# Lights.net
KiCad netlist of a schematic drawn in Altium Designer
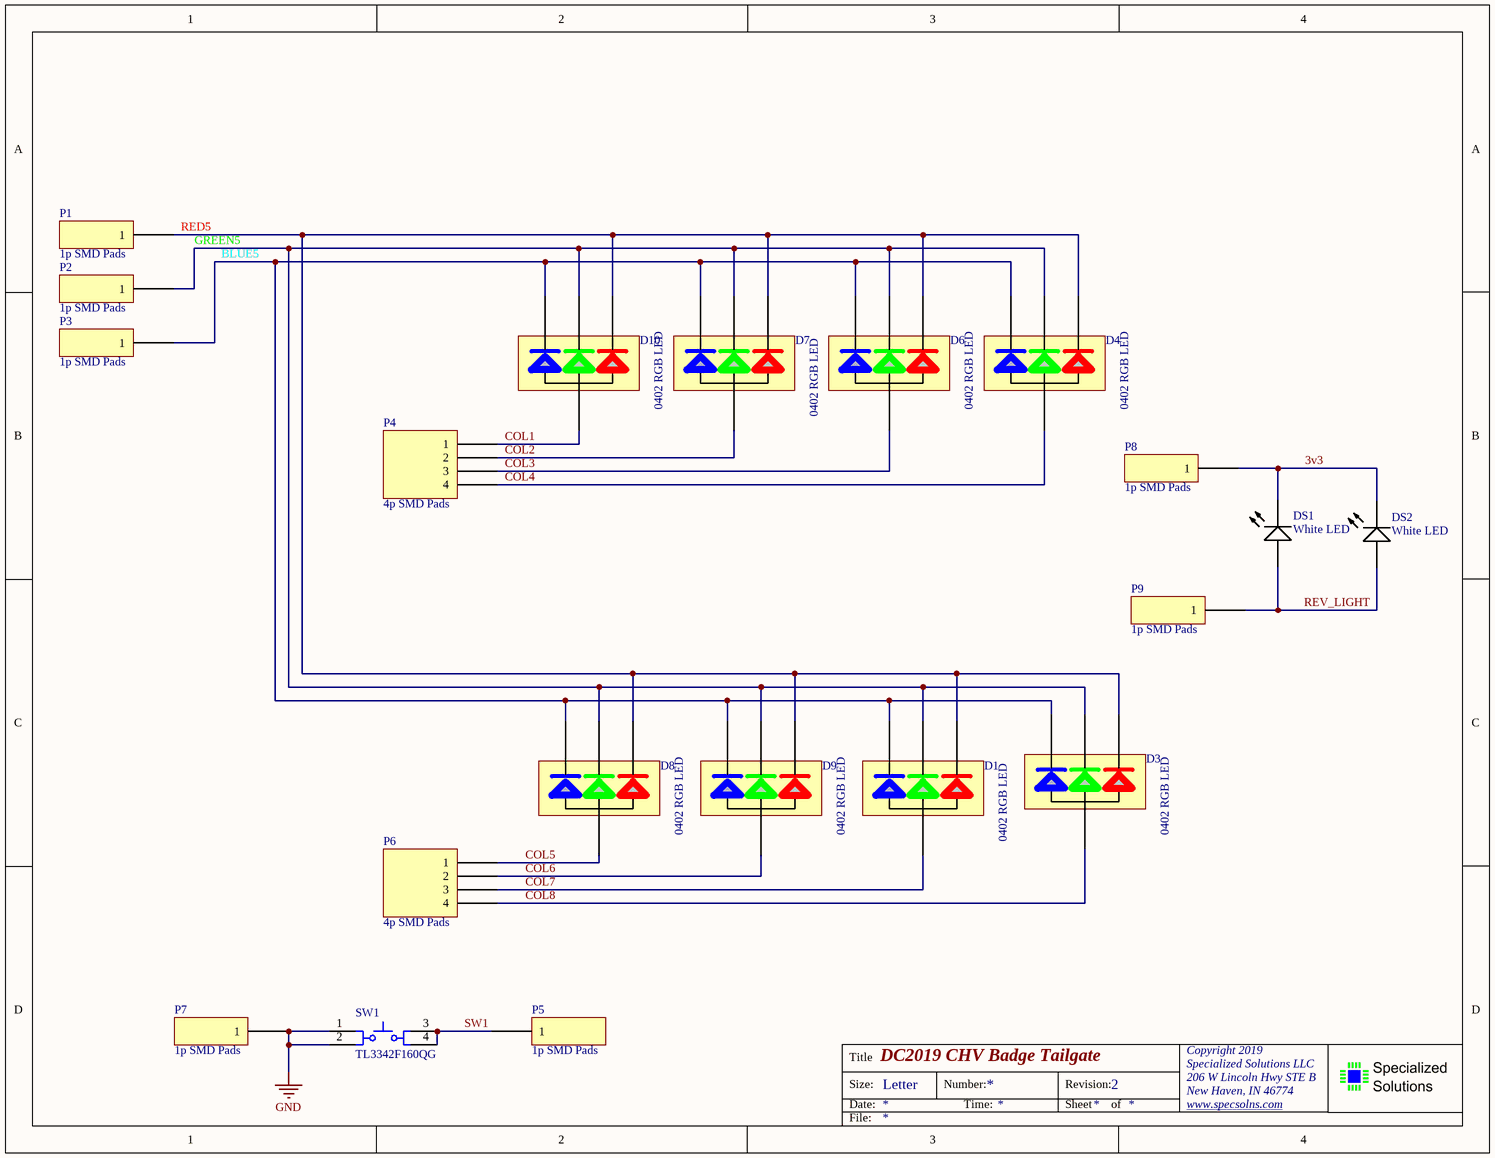
[diagram p0: Lights.SchDoc]

(export (version "E")
  (design (tool "Eeschema 10.0.6"))
  (components
    (comp (ref "D1")
      (value "0402 RGB LED")
      (footprint "0404 RGB LED")
      (libsource (lib "parts (fraker's conflicted copy 2018-10-08)") (part "0402 RGB LED"))
    )
    (comp (ref "D3")
      (value "0402 RGB LED")
      (footprint "0404 RGB LED")
      (libsource (lib "parts (fraker's conflicted copy 2018-10-08)") (part "0402 RGB LED"))
    )
    (comp (ref "D4")
      (value "0402 RGB LED")
      (footprint "0404 RGB LED")
      (libsource (lib "parts (fraker's conflicted copy 2018-10-08)") (part "0402 RGB LED"))
    )
    (comp (ref "D6")
      (value "0402 RGB LED")
      (footprint "0404 RGB LED")
      (libsource (lib "parts (fraker's conflicted copy 2018-10-08)") (part "0402 RGB LED"))
    )
    (comp (ref "D7")
      (value "0402 RGB LED")
      (footprint "0404 RGB LED")
      (libsource (lib "parts (fraker's conflicted copy 2018-10-08)") (part "0402 RGB LED"))
    )
    (comp (ref "D8")
      (value "0402 RGB LED")
      (footprint "0404 RGB LED")
      (libsource (lib "parts (fraker's conflicted copy 2018-10-08)") (part "0402 RGB LED"))
    )
    (comp (ref "D9")
      (value "0402 RGB LED")
      (footprint "0404 RGB LED")
      (libsource (lib "parts (fraker's conflicted copy 2018-10-08)") (part "0402 RGB LED"))
    )
    (comp (ref "D10")
      (value "0402 RGB LED")
      (footprint "0404 RGB LED")
      (libsource (lib "parts (fraker's conflicted copy 2018-10-08)") (part "0402 RGB LED"))
    )
    (comp (ref "DS1")
      (value "White LED")
      (footprint "EVRL-0402-2_V")
      (description "Chip LED, White, 5 V, 10 mA, 30 mW, -40 to 85 degC, 2-Pin SMD (0402), RoHS, Tape and Reel")
      (fields (field (name "MANUFACTURER") "Everlight Electronics"))
      (libsource (lib "Altium Content Vault") (part "LED-WHITE-AK-2"))
    )
    (comp (ref "DS2")
      (value "White LED")
      (footprint "EVRL-0402-2_V")
      (description "Chip LED, White, 5 V, 10 mA, 30 mW, -40 to 85 degC, 2-Pin SMD (0402), RoHS, Tape and Reel")
      (fields (field (name "MANUFACTURER") "Everlight Electronics"))
      (libsource (lib "Altium Content Vault") (part "LED-WHITE-AK-2"))
    )
    (comp (ref "P1") (value "1p SMD Pads") (footprint "1p SMD pad") (libsource (lib "parts") (part "1p SMD")))
    (comp (ref "P2") (value "1p SMD Pads") (footprint "1p SMD pad") (libsource (lib "parts") (part "1p SMD")))
    (comp (ref "P3") (value "1p SMD Pads") (footprint "1p SMD pad") (libsource (lib "parts") (part "1p SMD")))
    (comp (ref "P4") (value "4p SMD Pads") (footprint "4p SMD pad") (libsource (lib "parts") (part "4p SMD")))
    (comp (ref "P5")
      (value "1p SMD Pads")
      (footprint "1p SMD pad")
      (libsource (lib "parts (carol's conflicted copy 2019-04-30)") (part "1p SMD"))
    )
    (comp (ref "P6") (value "4p SMD Pads") (footprint "4p SMD pad") (libsource (lib "parts") (part "4p SMD")))
    (comp (ref "P7") (value "1p SMD Pads") (footprint "1p SMD pad") (libsource (lib "") (part "1p SMD_1")))
    (comp (ref "P8") (value "1p SMD Pads") (footprint "1p SMD pad") (libsource (lib "parts") (part "1p SMD")))
    (comp (ref "P9") (value "1p SMD Pads") (footprint "1p SMD pad") (libsource (lib "parts") (part "1p SMD")))
    (comp (ref "SW1")
      (value "TL3342F160QG")
      (footprint "ESWI-TL3342F160QG_V")
      (description "Switch, Tactile, SPST-NO, 50 mA, 12 V, 4-Pin SMD, RoHS, Tape and Reel")
      (fields (field (name "TOLERANCE") "20%"))
      (libsource (lib "Altium Content Vault") (part "SW-SPST-NO-4"))
    )
  )
  (nets
    (net (code "1") (name "/3v3") (class "Default")
      (node (ref "DS1") (pin "2") (pinfunction "K_2") (pintype "passive"))
      (node (ref "DS2") (pin "2") (pinfunction "K_2") (pintype "passive"))
      (node (ref "P8") (pin "1") (pinfunction "1_1") (pintype "passive"))
    )
    (net (code "2") (name "/BLUE5") (class "Default")
      (node (ref "D1") (pin "4") (pintype "passive"))
      (node (ref "D10") (pin "4") (pintype "passive"))
      (node (ref "D3") (pin "4") (pintype "passive"))
      (node (ref "D4") (pin "4") (pintype "passive"))
      (node (ref "D6") (pin "4") (pintype "passive"))
      (node (ref "D7") (pin "4") (pintype "passive"))
      (node (ref "D8") (pin "4") (pintype "passive"))
      (node (ref "D9") (pin "4") (pintype "passive"))
      (node (ref "P3") (pin "1") (pinfunction "1_1") (pintype "passive"))
    )
    (net (code "3") (name "/COL1") (class "Default")
      (node (ref "D10") (pin "1") (pintype "passive"))
      (node (ref "P4") (pin "1") (pinfunction "1_1") (pintype "passive"))
    )
    (net (code "4") (name "/COL2") (class "Default")
      (node (ref "D7") (pin "1") (pintype "passive"))
      (node (ref "P4") (pin "2") (pinfunction "2_2") (pintype "passive"))
    )
    (net (code "5") (name "/COL3") (class "Default")
      (node (ref "D6") (pin "1") (pintype "passive"))
      (node (ref "P4") (pin "3") (pinfunction "3_3") (pintype "passive"))
    )
    (net (code "6") (name "/COL4") (class "Default")
      (node (ref "D4") (pin "1") (pintype "passive"))
      (node (ref "P4") (pin "4") (pinfunction "4_4") (pintype "passive"))
    )
    (net (code "7") (name "/COL5") (class "Default")
      (node (ref "D8") (pin "1") (pintype "passive"))
      (node (ref "P6") (pin "1") (pinfunction "1_1") (pintype "passive"))
    )
    (net (code "8") (name "/COL6") (class "Default")
      (node (ref "D9") (pin "1") (pintype "passive"))
      (node (ref "P6") (pin "2") (pinfunction "2_2") (pintype "passive"))
    )
    (net (code "9") (name "/COL7") (class "Default")
      (node (ref "D1") (pin "1") (pintype "passive"))
      (node (ref "P6") (pin "3") (pinfunction "3_3") (pintype "passive"))
    )
    (net (code "10") (name "/COL8") (class "Default")
      (node (ref "D3") (pin "1") (pintype "passive"))
      (node (ref "P6") (pin "4") (pinfunction "4_4") (pintype "passive"))
    )
    (net (code "11") (name "/GREEN5") (class "Default")
      (node (ref "D1") (pin "3") (pintype "passive"))
      (node (ref "D10") (pin "3") (pintype "passive"))
      (node (ref "D3") (pin "3") (pintype "passive"))
      (node (ref "D4") (pin "3") (pintype "passive"))
      (node (ref "D6") (pin "3") (pintype "passive"))
      (node (ref "D7") (pin "3") (pintype "passive"))
      (node (ref "D8") (pin "3") (pintype "passive"))
      (node (ref "D9") (pin "3") (pintype "passive"))
      (node (ref "P2") (pin "1") (pinfunction "1_1") (pintype "passive"))
    )
    (net (code "12") (name "/RED5") (class "Default")
      (node (ref "D1") (pin "2") (pintype "passive"))
      (node (ref "D10") (pin "2") (pintype "passive"))
      (node (ref "D3") (pin "2") (pintype "passive"))
      (node (ref "D4") (pin "2") (pintype "passive"))
      (node (ref "D6") (pin "2") (pintype "passive"))
      (node (ref "D7") (pin "2") (pintype "passive"))
      (node (ref "D8") (pin "2") (pintype "passive"))
      (node (ref "D9") (pin "2") (pintype "passive"))
      (node (ref "P1") (pin "1") (pinfunction "1_1") (pintype "passive"))
    )
    (net (code "13") (name "/REV_LIGHT") (class "Default")
      (node (ref "DS1") (pin "1") (pinfunction "A_1") (pintype "passive"))
      (node (ref "DS2") (pin "1") (pinfunction "A_1") (pintype "passive"))
      (node (ref "P9") (pin "1") (pinfunction "1_1") (pintype "passive"))
    )
    (net (code "14") (name "/SW1") (class "Default")
      (node (ref "P5") (pin "1") (pinfunction "1_1") (pintype "passive"))
      (node (ref "SW1") (pin "3") (pinfunction "3_3") (pintype "passive"))
      (node (ref "SW1") (pin "4") (pinfunction "4_4") (pintype "passive"))
    )
    (net (code "15") (name "GND") (class "Default")
      (node (ref "P7") (pin "1") (pinfunction "1_1") (pintype "passive"))
      (node (ref "SW1") (pin "1") (pinfunction "1_1") (pintype "passive"))
      (node (ref "SW1") (pin "2") (pinfunction "2_2") (pintype "passive"))
    )
  )
)
